# GRBL3-10086-V10.net
KiCad netlist of a schematic drawn in Altium Designer
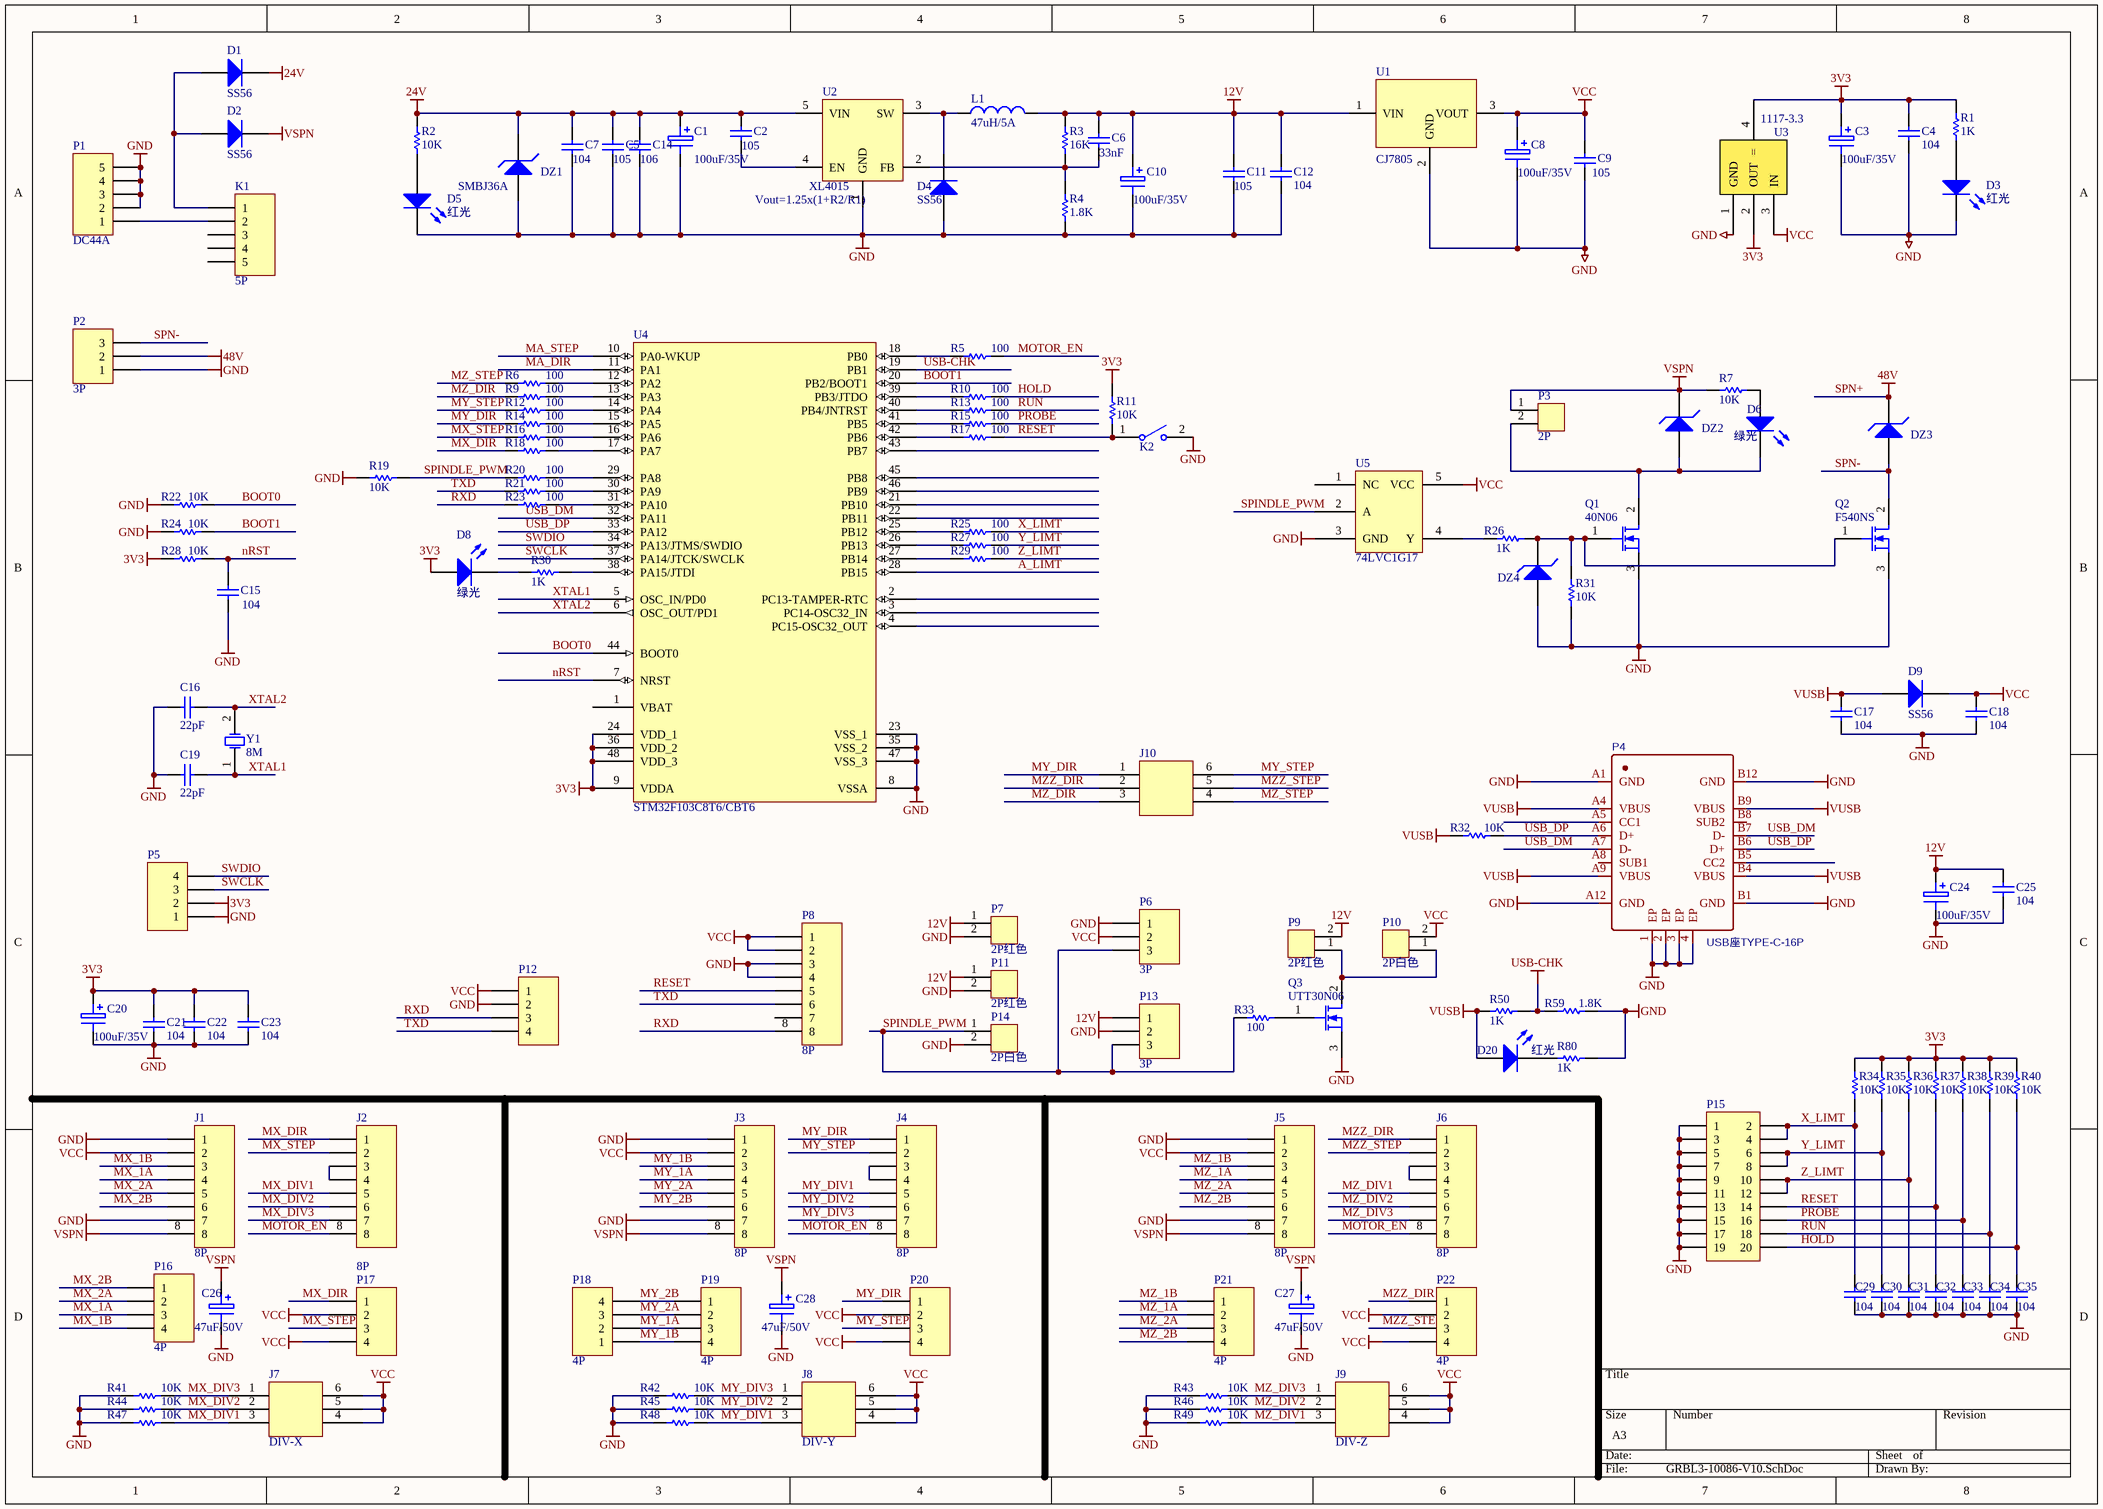
[diagram p0: GRBL3-10086-V10.SchDoc]

(export (version "E")
  (design (tool "Eeschema 10.0.6"))
  (components
    (comp (ref "C1") (value "100uF/35V") (footprint "电解电容贴片6x6") (libsource (lib "*") (part "ELECTRO1")))
    (comp (ref "C2") (value "105") (footprint "0603C") (libsource (lib "SCH封装库") (part "CAP")))
    (comp (ref "C3") (value "100uF/35V") (footprint "电解电容贴片6x6") (libsource (lib "*") (part "ELECTRO1")))
    (comp (ref "C4")
      (value "104")
      (footprint "0603C")
      (description "Capacitor (Semiconductor SIM Model)")
      (fields (field (name "PUBLISHER") "Altium Limited"))
      (libsource (lib "Miscellaneous Devices") (part "Cap Semi"))
    )
    (comp (ref "C5") (value "105") (footprint "0603C") (libsource (lib "SCH封装库") (part "CAP")))
    (comp (ref "C6") (value "33nF") (footprint "0603C") (libsource (lib "SCH封装库") (part "CAP")))
    (comp (ref "C7") (value "104") (footprint "0603C") (libsource (lib "SCH封装库") (part "CAP")))
    (comp (ref "C8") (value "100uF/35V") (footprint "电解电容贴片6x6") (libsource (lib "*") (part "ELECTRO1")))
    (comp (ref "C9")
      (value "105")
      (footprint "0603C")
      (description "Capacitor (Semiconductor SIM Model)")
      (fields (field (name "PUBLISHER") "Altium Limited"))
      (libsource (lib "Miscellaneous Devices") (part "Cap Semi"))
    )
    (comp (ref "C10") (value "100uF/35V") (footprint "电解电容贴片6x6") (libsource (lib "*") (part "ELECTRO1")))
    (comp (ref "C11") (value "105") (footprint "0603C") (libsource (lib "SCH封装库") (part "CAP")))
    (comp (ref "C12")
      (value "104")
      (footprint "0603C")
      (description "Capacitor (Semiconductor SIM Model)")
      (fields (field (name "PUBLISHER") "Altium Limited"))
      (libsource (lib "Miscellaneous Devices") (part "Cap Semi"))
    )
    (comp (ref "C14") (value "106") (footprint "1206C") (libsource (lib "SCH封装库") (part "CAP")))
    (comp (ref "C15")
      (value "104")
      (footprint "0603C")
      (description "Capacitor (Semiconductor SIM Model)")
      (fields (field (name "PUBLISHER") "Altium Limited"))
      (libsource (lib "Miscellaneous Devices") (part "Cap Semi"))
    )
    (comp (ref "C16")
      (value "22pF")
      (footprint "0603C")
      (description "Capacitor (Semiconductor SIM Model)")
      (fields (field (name "PUBLISHER") "Altium Limited"))
      (libsource (lib "Miscellaneous Devices") (part "Cap Semi"))
    )
    (comp (ref "C17")
      (value "104")
      (footprint "0603C")
      (description "Capacitor (Semiconductor SIM Model)")
      (fields (field (name "PUBLISHER") "Altium Limited"))
      (libsource (lib "Miscellaneous Devices") (part "Cap Semi"))
    )
    (comp (ref "C18")
      (value "104")
      (footprint "0603C")
      (description "Capacitor (Semiconductor SIM Model)")
      (fields (field (name "PUBLISHER") "Altium Limited"))
      (libsource (lib "Miscellaneous Devices") (part "Cap Semi"))
    )
    (comp (ref "C19")
      (value "22pF")
      (footprint "0603C")
      (description "Capacitor (Semiconductor SIM Model)")
      (fields (field (name "PUBLISHER") "Altium Limited"))
      (libsource (lib "Miscellaneous Devices") (part "Cap Semi"))
    )
    (comp (ref "C20") (value "100uF/35V") (footprint "电解电容贴片6x6") (libsource (lib "*") (part "ELECTRO1")))
    (comp (ref "C21") (value "104") (footprint "0603C") (libsource (lib "SCH封装库") (part "CAP")))
    (comp (ref "C22") (value "104") (footprint "0603C") (libsource (lib "SCH封装库") (part "CAP")))
    (comp (ref "C23") (value "104") (footprint "0603C") (libsource (lib "SCH封装库") (part "CAP")))
    (comp (ref "C24") (value "100uF/35V") (footprint "电解电容贴片6x6") (libsource (lib "*") (part "ELECTRO1")))
    (comp (ref "C25")
      (value "104")
      (footprint "0603C")
      (description "Capacitor (Semiconductor SIM Model)")
      (fields (field (name "PUBLISHER") "Altium Limited"))
      (libsource (lib "Miscellaneous Devices") (part "Cap Semi"))
    )
    (comp (ref "C26") (value "47uF/50V") (footprint "电解电容贴片6x6") (libsource (lib "*") (part "ELECTRO1")))
    (comp (ref "C27") (value "47uF/50V") (footprint "电解电容贴片6x6") (libsource (lib "*") (part "ELECTRO1")))
    (comp (ref "C28") (value "47uF/50V") (footprint "电解电容贴片6x6") (libsource (lib "*") (part "ELECTRO1")))
    (comp (ref "C29")
      (value "104")
      (footprint "0603C")
      (description "Capacitor (Semiconductor SIM Model)")
      (fields (field (name "PUBLISHER") "Altium Limited"))
      (libsource (lib "Miscellaneous Devices") (part "Cap Semi"))
    )
    (comp (ref "C30")
      (value "104")
      (footprint "0603C")
      (description "Capacitor (Semiconductor SIM Model)")
      (fields (field (name "PUBLISHER") "Altium Limited"))
      (libsource (lib "Miscellaneous Devices") (part "Cap Semi"))
    )
    (comp (ref "C31")
      (value "104")
      (footprint "0603C")
      (description "Capacitor (Semiconductor SIM Model)")
      (fields (field (name "PUBLISHER") "Altium Limited"))
      (libsource (lib "Miscellaneous Devices") (part "Cap Semi"))
    )
    (comp (ref "C32")
      (value "104")
      (footprint "0603C")
      (description "Capacitor (Semiconductor SIM Model)")
      (fields (field (name "PUBLISHER") "Altium Limited"))
      (libsource (lib "Miscellaneous Devices") (part "Cap Semi"))
    )
    (comp (ref "C33")
      (value "104")
      (footprint "0603C")
      (description "Capacitor (Semiconductor SIM Model)")
      (fields (field (name "PUBLISHER") "Altium Limited"))
      (libsource (lib "Miscellaneous Devices") (part "Cap Semi"))
    )
    (comp (ref "C34")
      (value "104")
      (footprint "0603C")
      (description "Capacitor (Semiconductor SIM Model)")
      (fields (field (name "PUBLISHER") "Altium Limited"))
      (libsource (lib "Miscellaneous Devices") (part "Cap Semi"))
    )
    (comp (ref "C35")
      (value "104")
      (footprint "0603C")
      (description "Capacitor (Semiconductor SIM Model)")
      (fields (field (name "PUBLISHER") "Altium Limited"))
      (libsource (lib "Miscellaneous Devices") (part "Cap Semi"))
    )
    (comp (ref "D1") (value "SS56") (footprint "SMA") (libsource (lib "SCH封装库") (part "1N4148")))
    (comp (ref "D2") (value "SS56") (footprint "SMA") (libsource (lib "SCH封装库") (part "1N4148")))
    (comp (ref "D3") (value "红光") (footprint "0603LED") (libsource (lib "SCH封装库") (part "LED")))
    (comp (ref "D4") (value "SS56") (footprint "SMA") (libsource (lib "SCH封装库") (part "1N4148")))
    (comp (ref "D5") (value "红光") (footprint "0603LED") (libsource (lib "SCH封装库") (part "LED")))
    (comp (ref "D6") (value "绿光") (footprint "0603LED") (libsource (lib "SCH封装库") (part "LED")))
    (comp (ref "D8") (value "绿光") (footprint "0603LED") (libsource (lib "SCH封装库") (part "LED")))
    (comp (ref "D9") (value "SS56") (footprint "SMA") (libsource (lib "SCH封装库") (part "1N4148")))
    (comp (ref "D20") (value "红光") (footprint "0603LED") (libsource (lib "SCH封装库") (part "LED")))
    (comp (ref "DZ1") (value "SMBJ36A") (footprint "SMB") (libsource (lib "SCH封装库") (part "稳压二极管")))
    (comp (ref "DZ2") (value "快恢复二极管RS5M") (footprint "SMC") (libsource (lib "SCH封装库") (part "稳压二极管")))
    (comp (ref "DZ3") (value "快恢复二极管RS5M") (footprint "SMC") (libsource (lib "SCH封装库") (part "稳压二极管")))
    (comp (ref "DZ4") (value "稳压二极管SMAZ10V") (footprint "SMA") (libsource (lib "SCH封装库") (part "稳压二极管")))
    (comp (ref "J1") (value "8P") (footprint "HDR1X8") (libsource (lib "SCH封装库") (part "8P")))
    (comp (ref "J2") (value "8P") (footprint "HDR1X8") (libsource (lib "SCH封装库") (part "8P")))
    (comp (ref "J3") (value "8P") (footprint "HDR1X8") (libsource (lib "SCH封装库") (part "8P")))
    (comp (ref "J4") (value "8P") (footprint "HDR1X8") (libsource (lib "SCH封装库") (part "8P")))
    (comp (ref "J5") (value "8P") (footprint "HDR1X8") (libsource (lib "SCH封装库") (part "8P")))
    (comp (ref "J6") (value "8P") (footprint "HDR1X8") (libsource (lib "SCH封装库") (part "8P")))
    (comp (ref "J7") (value "DIV-X") (footprint "HDR2X3") (libsource (lib "SCH封装库") (part "DIP6")))
    (comp (ref "J8") (value "DIV-Y") (footprint "HDR2X3") (libsource (lib "SCH封装库") (part "DIP6")))
    (comp (ref "J9") (value "DIV-Z") (footprint "HDR2X3") (libsource (lib "SCH封装库") (part "DIP6")))
    (comp (ref "J10") (value "DIV-Y") (footprint "HDR2X3") (libsource (lib "SCH封装库") (part "DIP6")))
    (comp (ref "K1") (value "5P") (footprint "拨动开关SS12D11") (libsource (lib "SCH封装库") (part "5P")))
    (comp (ref "K2") (value "开关") (footprint "按键6x6贴片5脚") (libsource (lib "SCH封装库") (part "开关")))
    (comp (ref "L1")
      (value "47uH/5A")
      (footprint "电感贴片12x12")
      (description "Inductor")
      (fields (field (name "PUBLISHER") "Altium Limited"))
      (libsource (lib "SCH封装库") (part "Inductor"))
    )
    (comp (ref "P1")
      (value "DC44A")
      (footprint "DC0044A")
      (description "Header, 5-Pin")
      (fields (field (name "PUBLISHER") "Altium Limited"))
      (libsource (lib "Miscellaneous Connectors") (part "Header 5"))
    )
    (comp (ref "P2") (value "3P") (footprint "直插座3P-KF300") (libsource (lib "") (part "3P_1")))
    (comp (ref "P3") (value "2P") (footprint "VH3.96-2P直插座") (libsource (lib "SCH封装库") (part "2P")))
    (comp (ref "P4")
      (value "USB座TYPE-C-16P")
      (footprint "USB-TYPE-C-16P")
      (fields
        (field (name "BOM_SUPPLIER PART") "C709358")
        (field (name "BOM_MANUFACTURER PART") "KH-TYPE-C-16P-T")
        (field (name "CONTRIBUTOR") "LCSC")
      )
      (libsource (lib "SCH封装库") (part "USB座TYPE-C-16P"))
    )
    (comp (ref "P5") (value "~") (footprint "SIP4") (libsource (lib "") (part "4P_1")))
    (comp (ref "P6") (value "3P") (footprint "SIP3") (libsource (lib "SCH封装库") (part "3P")))
    (comp (ref "P7") (value "2P红色") (footprint "HDR1X2_CON") (libsource (lib "SCH封装库") (part "2P")))
    (comp (ref "P8") (value "8P") (footprint "IDC8") (libsource (lib "SCH封装库") (part "8P")))
    (comp (ref "P9") (value "2P红色") (footprint "HDR1X2_CON") (libsource (lib "") (part "2P_1")))
    (comp (ref "P10") (value "2P白色") (footprint "HDR1X2_CON") (libsource (lib "") (part "2P_1")))
    (comp (ref "P11") (value "2P红色") (footprint "HDR1X2_CON") (libsource (lib "SCH封装库") (part "2P")))
    (comp (ref "P12") (value "~") (footprint "SIP4") (libsource (lib "SCH封装库") (part "4P")))
    (comp (ref "P13") (value "3P") (footprint "HDR1X3_CON") (libsource (lib "SCH封装库") (part "3P")))
    (comp (ref "P14") (value "2P白色") (footprint "HDR1X2_CON") (libsource (lib "SCH封装库") (part "2P")))
    (comp (ref "P15")
      (value "Header 10X2H")
      (footprint "HDR2X10")
      (description "Header, 10-Pin, Dual row, Right Angle")
      (fields (field (name "PUBLISHER") "Altium Limited"))
      (libsource (lib "Miscellaneous Connectors") (part "Header 10X2H"))
    )
    (comp (ref "P16") (value "4P") (footprint "HDR1X4_CON") (libsource (lib "SCH封装库") (part "4P")))
    (comp (ref "P17") (value "~") (footprint "SIP4") (libsource (lib "SCH封装库") (part "4P")))
    (comp (ref "P18") (value "4P") (footprint "HDR1X4_CON") (libsource (lib "") (part "4P_1")))
    (comp (ref "P19") (value "4P") (footprint "HDR1X4_CON") (libsource (lib "SCH封装库") (part "4P")))
    (comp (ref "P20") (value "~") (footprint "SIP4") (libsource (lib "SCH封装库") (part "4P")))
    (comp (ref "P21") (value "4P") (footprint "HDR1X4_CON") (libsource (lib "SCH封装库") (part "4P")))
    (comp (ref "P22") (value "4P") (footprint "SIP4") (libsource (lib "SCH封装库") (part "4P")))
    (comp (ref "Q1")
      (value "40N06")
      (footprint "TO-252")
      (description "N-Channel MOSFET")
      (fields (field (name "PUBLISHER") "Altium Limited"))
      (libsource (lib "SCH封装库") (part "MOSFET-N"))
    )
    (comp (ref "Q2")
      (value "F540NS")
      (footprint "TO-263-2")
      (description "N-Channel MOSFET")
      (fields (field (name "PUBLISHER") "Altium Limited"))
      (libsource (lib "SCH封装库") (part "MOSFET-N"))
    )
    (comp (ref "Q3")
      (value "UTT30N06")
      (footprint "TO-252")
      (description "N-Channel MOSFET")
      (fields (field (name "PUBLISHER") "Altium Limited"))
      (libsource (lib "SCH封装库") (part "MOSFET-N"))
    )
    (comp (ref "R1")
      (value "1K")
      (footprint "0603R")
      (description "Resistor")
      (fields (field (name "PUBLISHER") "Altium Limited"))
      (libsource (lib "SCH封装库") (part "RES"))
    )
    (comp (ref "R2")
      (value "10K")
      (footprint "0603R")
      (description "Resistor")
      (fields (field (name "PUBLISHER") "Altium Limited"))
      (libsource (lib "SCH封装库") (part "RES"))
    )
    (comp (ref "R3")
      (value "16K")
      (footprint "0603R")
      (description "Resistor")
      (fields (field (name "PUBLISHER") "Altium Limited"))
      (libsource (lib "SCH封装库") (part "RES"))
    )
    (comp (ref "R4")
      (value "1.8K")
      (footprint "0603R")
      (description "Resistor")
      (fields (field (name "PUBLISHER") "Altium Limited"))
      (libsource (lib "SCH封装库") (part "RES"))
    )
    (comp (ref "R5")
      (value "100")
      (footprint "0603R")
      (description "Resistor")
      (fields (field (name "PUBLISHER") "Altium Limited"))
      (libsource (lib "SCH封装库") (part "RES"))
    )
    (comp (ref "R6")
      (value "100")
      (footprint "0603R")
      (description "Resistor")
      (fields (field (name "PUBLISHER") "Altium Limited"))
      (libsource (lib "SCH封装库") (part "RES"))
    )
    (comp (ref "R7")
      (value "10K")
      (footprint "0603R")
      (description "Resistor")
      (fields (field (name "PUBLISHER") "Altium Limited"))
      (libsource (lib "SCH封装库") (part "RES"))
    )
    (comp (ref "R9")
      (value "100")
      (footprint "0603R")
      (description "Resistor")
      (fields (field (name "PUBLISHER") "Altium Limited"))
      (libsource (lib "SCH封装库") (part "RES"))
    )
    (comp (ref "R10")
      (value "100")
      (footprint "0603R")
      (description "Resistor")
      (fields (field (name "PUBLISHER") "Altium Limited"))
      (libsource (lib "SCH封装库") (part "RES"))
    )
    (comp (ref "R11")
      (value "10K")
      (footprint "0603R")
      (description "Resistor")
      (fields (field (name "PUBLISHER") "Altium Limited"))
      (libsource (lib "SCH封装库") (part "RES"))
    )
    (comp (ref "R12")
      (value "100")
      (footprint "0603R")
      (description "Resistor")
      (fields (field (name "PUBLISHER") "Altium Limited"))
      (libsource (lib "SCH封装库") (part "RES"))
    )
    (comp (ref "R13")
      (value "100")
      (footprint "0603R")
      (description "Resistor")
      (fields (field (name "PUBLISHER") "Altium Limited"))
      (libsource (lib "SCH封装库") (part "RES"))
    )
    (comp (ref "R14")
      (value "100")
      (footprint "0603R")
      (description "Resistor")
      (fields (field (name "PUBLISHER") "Altium Limited"))
      (libsource (lib "SCH封装库") (part "RES"))
    )
    (comp (ref "R15")
      (value "100")
      (footprint "0603R")
      (description "Resistor")
      (fields (field (name "PUBLISHER") "Altium Limited"))
      (libsource (lib "SCH封装库") (part "RES"))
    )
    (comp (ref "R16")
      (value "100")
      (footprint "0603R")
      (description "Resistor")
      (fields (field (name "PUBLISHER") "Altium Limited"))
      (libsource (lib "SCH封装库") (part "RES"))
    )
    (comp (ref "R17")
      (value "100")
      (footprint "0603R")
      (description "Resistor")
      (fields (field (name "PUBLISHER") "Altium Limited"))
      (libsource (lib "SCH封装库") (part "RES"))
    )
    (comp (ref "R18")
      (value "100")
      (footprint "0603R")
      (description "Resistor")
      (fields (field (name "PUBLISHER") "Altium Limited"))
      (libsource (lib "SCH封装库") (part "RES"))
    )
    (comp (ref "R19")
      (value "10K")
      (footprint "0603R")
      (description "Resistor")
      (fields (field (name "PUBLISHER") "Altium Limited"))
      (libsource (lib "SCH封装库") (part "RES"))
    )
    (comp (ref "R20")
      (value "100")
      (footprint "0603R")
      (description "Resistor")
      (fields (field (name "PUBLISHER") "Altium Limited"))
      (libsource (lib "SCH封装库") (part "RES"))
    )
    (comp (ref "R21")
      (value "100")
      (footprint "0603R")
      (description "Resistor")
      (fields (field (name "PUBLISHER") "Altium Limited"))
      (libsource (lib "SCH封装库") (part "RES"))
    )
    (comp (ref "R22")
      (value "10K")
      (footprint "0603R")
      (description "Resistor")
      (fields (field (name "Comment") "10k") (field (name "PUBLISHER") "Altium Limited"))
      (libsource (lib "SCH封装库") (part "RES"))
    )
    (comp (ref "R23")
      (value "100")
      (footprint "0603R")
      (description "Resistor")
      (fields (field (name "PUBLISHER") "Altium Limited"))
      (libsource (lib "SCH封装库") (part "RES"))
    )
    (comp (ref "R24")
      (value "10K")
      (footprint "0603R")
      (description "Resistor")
      (fields (field (name "Comment") "10k") (field (name "PUBLISHER") "Altium Limited"))
      (libsource (lib "SCH封装库") (part "RES"))
    )
    (comp (ref "R25")
      (value "100")
      (footprint "0603R")
      (description "Resistor")
      (fields (field (name "PUBLISHER") "Altium Limited"))
      (libsource (lib "SCH封装库") (part "RES"))
    )
    (comp (ref "R26")
      (value "1K")
      (footprint "0603R")
      (description "Resistor")
      (fields (field (name "PUBLISHER") "Altium Limited"))
      (libsource (lib "SCH封装库") (part "RES"))
    )
    (comp (ref "R27")
      (value "100")
      (footprint "0603R")
      (description "Resistor")
      (fields (field (name "PUBLISHER") "Altium Limited"))
      (libsource (lib "SCH封装库") (part "RES"))
    )
    (comp (ref "R28")
      (value "10K")
      (footprint "0603R")
      (description "Resistor")
      (fields (field (name "Comment") "10k") (field (name "PUBLISHER") "Altium Limited"))
      (libsource (lib "SCH封装库") (part "RES"))
    )
    (comp (ref "R29")
      (value "100")
      (footprint "0603R")
      (description "Resistor")
      (fields (field (name "PUBLISHER") "Altium Limited"))
      (libsource (lib "SCH封装库") (part "RES"))
    )
    (comp (ref "R30")
      (value "1K")
      (footprint "0603R")
      (description "Resistor")
      (fields (field (name "PUBLISHER") "Altium Limited"))
      (libsource (lib "SCH封装库") (part "RES"))
    )
    (comp (ref "R31")
      (value "10K")
      (footprint "0603R")
      (description "Resistor")
      (fields (field (name "PUBLISHER") "Altium Limited"))
      (libsource (lib "SCH封装库") (part "RES"))
    )
    (comp (ref "R32")
      (value "10K")
      (footprint "0603R")
      (description "Resistor")
      (fields (field (name "PUBLISHER") "Altium Limited"))
      (libsource (lib "SCH封装库") (part "RES"))
    )
    (comp (ref "R33")
      (value "100")
      (footprint "0603R")
      (description "Resistor")
      (fields (field (name "PUBLISHER") "Altium Limited"))
      (libsource (lib "SCH封装库") (part "RES"))
    )
    (comp (ref "R34")
      (value "10K")
      (footprint "0603R")
      (description "Resistor")
      (fields (field (name "PUBLISHER") "Altium Limited"))
      (libsource (lib "SCH封装库") (part "RES"))
    )
    (comp (ref "R35")
      (value "10K")
      (footprint "0603R")
      (description "Resistor")
      (fields (field (name "PUBLISHER") "Altium Limited"))
      (libsource (lib "SCH封装库") (part "RES"))
    )
    (comp (ref "R36")
      (value "10K")
      (footprint "0603R")
      (description "Resistor")
      (fields (field (name "PUBLISHER") "Altium Limited"))
      (libsource (lib "SCH封装库") (part "RES"))
    )
    (comp (ref "R37")
      (value "10K")
      (footprint "0603R")
      (description "Resistor")
      (fields (field (name "PUBLISHER") "Altium Limited"))
      (libsource (lib "SCH封装库") (part "RES"))
    )
    (comp (ref "R38")
      (value "10K")
      (footprint "0603R")
      (description "Resistor")
      (fields (field (name "PUBLISHER") "Altium Limited"))
      (libsource (lib "SCH封装库") (part "RES"))
    )
    (comp (ref "R39")
      (value "10K")
      (footprint "0603R")
      (description "Resistor")
      (fields (field (name "PUBLISHER") "Altium Limited"))
      (libsource (lib "SCH封装库") (part "RES"))
    )
    (comp (ref "R40")
      (value "10K")
      (footprint "0603R")
      (description "Resistor")
      (fields (field (name "PUBLISHER") "Altium Limited"))
      (libsource (lib "SCH封装库") (part "RES"))
    )
    (comp (ref "R41")
      (value "10K")
      (footprint "0603R")
      (description "Resistor")
      (fields (field (name "PUBLISHER") "Altium Limited"))
      (libsource (lib "SCH封装库") (part "RES"))
    )
    (comp (ref "R42")
      (value "10K")
      (footprint "0603R")
      (description "Resistor")
      (fields (field (name "PUBLISHER") "Altium Limited"))
      (libsource (lib "SCH封装库") (part "RES"))
    )
    (comp (ref "R43")
      (value "10K")
      (footprint "0603R")
      (description "Resistor")
      (fields (field (name "PUBLISHER") "Altium Limited"))
      (libsource (lib "SCH封装库") (part "RES"))
    )
    (comp (ref "R44")
      (value "10K")
      (footprint "0603R")
      (description "Resistor")
      (fields (field (name "PUBLISHER") "Altium Limited"))
      (libsource (lib "SCH封装库") (part "RES"))
    )
    (comp (ref "R45")
      (value "10K")
      (footprint "0603R")
      (description "Resistor")
      (fields (field (name "PUBLISHER") "Altium Limited"))
      (libsource (lib "SCH封装库") (part "RES"))
    )
    (comp (ref "R46")
      (value "10K")
      (footprint "0603R")
      (description "Resistor")
      (fields (field (name "PUBLISHER") "Altium Limited"))
      (libsource (lib "SCH封装库") (part "RES"))
    )
    (comp (ref "R47")
      (value "10K")
      (footprint "0603R")
      (description "Resistor")
      (fields (field (name "PUBLISHER") "Altium Limited"))
      (libsource (lib "SCH封装库") (part "RES"))
    )
    (comp (ref "R48")
      (value "10K")
      (footprint "0603R")
      (description "Resistor")
      (fields (field (name "PUBLISHER") "Altium Limited"))
      (libsource (lib "SCH封装库") (part "RES"))
    )
    (comp (ref "R49")
      (value "10K")
      (footprint "0603R")
      (description "Resistor")
      (fields (field (name "PUBLISHER") "Altium Limited"))
      (libsource (lib "SCH封装库") (part "RES"))
    )
    (comp (ref "R50")
      (value "1K")
      (footprint "0603R")
      (description "Resistor")
      (fields (field (name "PUBLISHER") "Altium Limited"))
      (libsource (lib "SCH封装库") (part "RES"))
    )
    (comp (ref "R59")
      (value "1.8K")
      (footprint "0603R")
      (description "Resistor")
      (fields (field (name "PUBLISHER") "Altium Limited"))
      (libsource (lib "SCH封装库") (part "RES"))
    )
    (comp (ref "R80")
      (value "1K")
      (footprint "0603R")
      (description "Resistor")
      (fields (field (name "PUBLISHER") "Altium Limited"))
      (libsource (lib "SCH封装库") (part "RES"))
    )
    (comp (ref "U1") (value "CJ7805") (footprint "TO-263-2") (libsource (lib "SCH封装库") (part "7805")))
    (comp (ref "U2") (value "XL4015") (footprint "TO-263") (libsource (lib "SCH封装库") (part "XL4005")))
    (comp (ref "U3") (value "1117-3.3") (footprint "SOT-223") (libsource (lib "Party600") (part "LM1117")))
    (comp (ref "U4")
      (value "STM32F103C8T6/CBT6")
      (footprint "LQFP48")
      (description "STM32 ARM-based 32-bit MCU with 32 Kbytes Flash, 48-pin LQFP, Industrial Temperature")
      (fields (field (name "PUBLISHER") "*"))
      (libsource (lib "ST Microcontroller 32-Bit STM32 SCH") (part "STM32F103C6T6"))
    )
    (comp (ref "U5") (value "74LVC1G17") (footprint "SOT-23-5") (libsource (lib "SCH封装库") (part "74LVC1G17")))
    (comp (ref "Y1")
      (value "8M")
      (footprint "晶振贴片")
      (description "Crystal Oscillator")
      (fields (field (name "PUBLISHER") "Altium Limited"))
      (libsource (lib "Miscellaneous Devices") (part "XTAL"))
    )
  )
  (nets
    (net (code "1") (name "/A_LIMT") (class "Default")
      (node (ref "U4") (pin "28") (pinfunction "PB15_28") (pintype "bidirectional"))
    )
    (net (code "2") (name "/BOOT0") (class "Default")
      (node (ref "R22") (pin "2") (pinfunction "2_2") (pintype "passive"))
      (node (ref "U4") (pin "44") (pinfunction "BOOT0_44") (pintype "input"))
    )
    (net (code "3") (name "/BOOT1") (class "Default")
      (node (ref "R24") (pin "2") (pinfunction "2_2") (pintype "passive"))
      (node (ref "U4") (pin "20") (pinfunction "PB2/BOOT1_20") (pintype "bidirectional"))
    )
    (net (code "4") (name "/HOLD") (class "Default")
      (node (ref "C35") (pin "2") (pinfunction "2_2") (pintype "passive"))
      (node (ref "P15") (pin "20") (pinfunction "20_20") (pintype "passive"))
      (node (ref "R10") (pin "2") (pinfunction "2_2") (pintype "passive"))
      (node (ref "R40") (pin "1") (pinfunction "1_1") (pintype "passive"))
    )
    (net (code "5") (name "/MA_DIR") (class "Default")
      (node (ref "U4") (pin "11") (pinfunction "PA1_11") (pintype "bidirectional"))
    )
    (net (code "6") (name "/MA_STEP") (class "Default")
      (node (ref "U4") (pin "10") (pinfunction "PA0-WKUP_10") (pintype "bidirectional"))
    )
    (net (code "7") (name "/MOTOR_EN") (class "Default")
      (node (ref "J2") (pin "8") (pinfunction "8_8") (pintype "passive"))
      (node (ref "J4") (pin "8") (pinfunction "8_8") (pintype "passive"))
      (node (ref "J6") (pin "8") (pinfunction "8_8") (pintype "passive"))
      (node (ref "R5") (pin "2") (pinfunction "2_2") (pintype "passive"))
    )
    (net (code "8") (name "/MX_1A") (class "Default")
      (node (ref "J1") (pin "4") (pinfunction "4_4") (pintype "passive"))
      (node (ref "P16") (pin "3") (pinfunction "3_3") (pintype "passive"))
    )
    (net (code "9") (name "/MX_1B") (class "Default")
      (node (ref "J1") (pin "3") (pinfunction "3_3") (pintype "passive"))
      (node (ref "P16") (pin "4") (pinfunction "4_4") (pintype "passive"))
    )
    (net (code "10") (name "/MX_2A") (class "Default")
      (node (ref "J1") (pin "5") (pinfunction "5_5") (pintype "passive"))
      (node (ref "P16") (pin "2") (pinfunction "2_2") (pintype "passive"))
    )
    (net (code "11") (name "/MX_2B") (class "Default")
      (node (ref "J1") (pin "6") (pinfunction "6_6") (pintype "passive"))
      (node (ref "P16") (pin "1") (pinfunction "1_1") (pintype "passive"))
    )
    (net (code "12") (name "/MX_DIR") (class "Default")
      (node (ref "J2") (pin "1") (pinfunction "1_1") (pintype "passive"))
      (node (ref "P17") (pin "1") (pinfunction "1_1") (pintype "passive"))
      (node (ref "R18") (pin "1") (pinfunction "1_1") (pintype "passive"))
    )
    (net (code "13") (name "/MX_DIV1") (class "Default")
      (node (ref "J2") (pin "5") (pinfunction "5_5") (pintype "passive"))
      (node (ref "J7") (pin "3") (pinfunction "3_3") (pintype "passive"))
      (node (ref "R47") (pin "1") (pinfunction "1_1") (pintype "passive"))
    )
    (net (code "14") (name "/MX_DIV2") (class "Default")
      (node (ref "J2") (pin "6") (pinfunction "6_6") (pintype "passive"))
      (node (ref "J7") (pin "2") (pinfunction "2_2") (pintype "passive"))
      (node (ref "R44") (pin "1") (pinfunction "1_1") (pintype "passive"))
    )
    (net (code "15") (name "/MX_DIV3") (class "Default")
      (node (ref "J2") (pin "7") (pinfunction "7_7") (pintype "passive"))
      (node (ref "J7") (pin "1") (pinfunction "1_1") (pintype "passive"))
      (node (ref "R41") (pin "1") (pinfunction "1_1") (pintype "passive"))
    )
    (net (code "16") (name "/MX_STEP") (class "Default")
      (node (ref "J2") (pin "2") (pinfunction "2_2") (pintype "passive"))
      (node (ref "P17") (pin "3") (pinfunction "3_3") (pintype "passive"))
      (node (ref "R16") (pin "1") (pinfunction "1_1") (pintype "passive"))
    )
    (net (code "17") (name "/MY_1A") (class "Default")
      (node (ref "J3") (pin "4") (pinfunction "4_4") (pintype "passive"))
      (node (ref "P18") (pin "2") (pinfunction "2_2") (pintype "passive"))
      (node (ref "P19") (pin "3") (pinfunction "3_3") (pintype "passive"))
    )
    (net (code "18") (name "/MY_1B") (class "Default")
      (node (ref "J3") (pin "3") (pinfunction "3_3") (pintype "passive"))
      (node (ref "P18") (pin "1") (pinfunction "1_1") (pintype "passive"))
      (node (ref "P19") (pin "4") (pinfunction "4_4") (pintype "passive"))
    )
    (net (code "19") (name "/MY_2A") (class "Default")
      (node (ref "J3") (pin "5") (pinfunction "5_5") (pintype "passive"))
      (node (ref "P18") (pin "3") (pinfunction "3_3") (pintype "passive"))
      (node (ref "P19") (pin "2") (pinfunction "2_2") (pintype "passive"))
    )
    (net (code "20") (name "/MY_2B") (class "Default")
      (node (ref "J3") (pin "6") (pinfunction "6_6") (pintype "passive"))
      (node (ref "P18") (pin "4") (pinfunction "4_4") (pintype "passive"))
      (node (ref "P19") (pin "1") (pinfunction "1_1") (pintype "passive"))
    )
    (net (code "21") (name "/MY_DIR") (class "Default")
      (node (ref "J10") (pin "1") (pinfunction "1_1") (pintype "passive"))
      (node (ref "J4") (pin "1") (pinfunction "1_1") (pintype "passive"))
      (node (ref "P20") (pin "1") (pinfunction "1_1") (pintype "passive"))
      (node (ref "R14") (pin "1") (pinfunction "1_1") (pintype "passive"))
    )
    (net (code "22") (name "/MY_DIV1") (class "Default")
      (node (ref "J4") (pin "5") (pinfunction "5_5") (pintype "passive"))
      (node (ref "J8") (pin "3") (pinfunction "3_3") (pintype "passive"))
      (node (ref "R48") (pin "1") (pinfunction "1_1") (pintype "passive"))
    )
    (net (code "23") (name "/MY_DIV2") (class "Default")
      (node (ref "J4") (pin "6") (pinfunction "6_6") (pintype "passive"))
      (node (ref "J8") (pin "2") (pinfunction "2_2") (pintype "passive"))
      (node (ref "R45") (pin "1") (pinfunction "1_1") (pintype "passive"))
    )
    (net (code "24") (name "/MY_DIV3") (class "Default")
      (node (ref "J4") (pin "7") (pinfunction "7_7") (pintype "passive"))
      (node (ref "J8") (pin "1") (pinfunction "1_1") (pintype "passive"))
      (node (ref "R42") (pin "1") (pinfunction "1_1") (pintype "passive"))
    )
    (net (code "25") (name "/MY_STEP") (class "Default")
      (node (ref "J10") (pin "6") (pinfunction "6_6") (pintype "passive"))
      (node (ref "J4") (pin "2") (pinfunction "2_2") (pintype "passive"))
      (node (ref "P20") (pin "3") (pinfunction "3_3") (pintype "passive"))
      (node (ref "R12") (pin "1") (pinfunction "1_1") (pintype "passive"))
    )
    (net (code "26") (name "/MZZ_DIR") (class "Default")
      (node (ref "J10") (pin "2") (pinfunction "2_2") (pintype "passive"))
      (node (ref "J6") (pin "1") (pinfunction "1_1") (pintype "passive"))
      (node (ref "P22") (pin "1") (pinfunction "1_1") (pintype "passive"))
    )
    (net (code "27") (name "/MZZ_STEP") (class "Default")
      (node (ref "J10") (pin "5") (pinfunction "5_5") (pintype "passive"))
      (node (ref "J6") (pin "2") (pinfunction "2_2") (pintype "passive"))
      (node (ref "P22") (pin "3") (pinfunction "3_3") (pintype "passive"))
    )
    (net (code "28") (name "/MZ_1A") (class "Default")
      (node (ref "J5") (pin "4") (pinfunction "4_4") (pintype "passive"))
      (node (ref "P21") (pin "2") (pinfunction "2_2") (pintype "passive"))
    )
    (net (code "29") (name "/MZ_1B") (class "Default")
      (node (ref "J5") (pin "3") (pinfunction "3_3") (pintype "passive"))
      (node (ref "P21") (pin "1") (pinfunction "1_1") (pintype "passive"))
    )
    (net (code "30") (name "/MZ_2A") (class "Default")
      (node (ref "J5") (pin "5") (pinfunction "5_5") (pintype "passive"))
      (node (ref "P21") (pin "3") (pinfunction "3_3") (pintype "passive"))
    )
    (net (code "31") (name "/MZ_2B") (class "Default")
      (node (ref "J5") (pin "6") (pinfunction "6_6") (pintype "passive"))
      (node (ref "P21") (pin "4") (pinfunction "4_4") (pintype "passive"))
    )
    (net (code "32") (name "/MZ_DIR") (class "Default")
      (node (ref "J10") (pin "3") (pinfunction "3_3") (pintype "passive"))
      (node (ref "R9") (pin "1") (pinfunction "1_1") (pintype "passive"))
    )
    (net (code "33") (name "/MZ_DIV1") (class "Default")
      (node (ref "J6") (pin "5") (pinfunction "5_5") (pintype "passive"))
      (node (ref "J9") (pin "3") (pinfunction "3_3") (pintype "passive"))
      (node (ref "R49") (pin "1") (pinfunction "1_1") (pintype "passive"))
    )
    (net (code "34") (name "/MZ_DIV2") (class "Default")
      (node (ref "J6") (pin "6") (pinfunction "6_6") (pintype "passive"))
      (node (ref "J9") (pin "2") (pinfunction "2_2") (pintype "passive"))
      (node (ref "R46") (pin "1") (pinfunction "1_1") (pintype "passive"))
    )
    (net (code "35") (name "/MZ_DIV3") (class "Default")
      (node (ref "J6") (pin "7") (pinfunction "7_7") (pintype "passive"))
      (node (ref "J9") (pin "1") (pinfunction "1_1") (pintype "passive"))
      (node (ref "R43") (pin "1") (pinfunction "1_1") (pintype "passive"))
    )
    (net (code "36") (name "/MZ_STEP") (class "Default")
      (node (ref "J10") (pin "4") (pinfunction "4_4") (pintype "passive"))
      (node (ref "R6") (pin "1") (pinfunction "1_1") (pintype "passive"))
    )
    (net (code "37") (name "/PROBE") (class "Default")
      (node (ref "C33") (pin "2") (pinfunction "2_2") (pintype "passive"))
      (node (ref "P15") (pin "16") (pinfunction "16_16") (pintype "passive"))
      (node (ref "R15") (pin "2") (pinfunction "2_2") (pintype "passive"))
      (node (ref "R38") (pin "1") (pinfunction "1_1") (pintype "passive"))
    )
    (net (code "38") (name "/RESET") (class "Default")
      (node (ref "C32") (pin "2") (pinfunction "2_2") (pintype "passive"))
      (node (ref "K2") (pin "1") (pinfunction "COMMON_1") (pintype "passive"))
      (node (ref "P15") (pin "14") (pinfunction "14_14") (pintype "passive"))
      (node (ref "P8") (pin "5") (pinfunction "5_5") (pintype "passive"))
      (node (ref "R11") (pin "1") (pinfunction "1_1") (pintype "passive"))
      (node (ref "R17") (pin "2") (pinfunction "2_2") (pintype "passive"))
      (node (ref "R37") (pin "1") (pinfunction "1_1") (pintype "passive"))
    )
    (net (code "39") (name "/RUN") (class "Default")
      (node (ref "C34") (pin "2") (pinfunction "2_2") (pintype "passive"))
      (node (ref "P15") (pin "18") (pinfunction "18_18") (pintype "passive"))
      (node (ref "R13") (pin "2") (pinfunction "2_2") (pintype "passive"))
      (node (ref "R39") (pin "1") (pinfunction "1_1") (pintype "passive"))
    )
    (net (code "40") (name "/RXD") (class "Default")
      (node (ref "P12") (pin "3") (pinfunction "3_3") (pintype "passive"))
      (node (ref "P8") (pin "8") (pinfunction "8_8") (pintype "passive"))
      (node (ref "R23") (pin "1") (pinfunction "1_1") (pintype "passive"))
    )
    (net (code "41") (name "/SPINDLE_PWM") (class "Default")
      (node (ref "P13") (pin "3") (pinfunction "3_3") (pintype "passive"))
      (node (ref "P14") (pin "1") (pintype "passive"))
      (node (ref "P6") (pin "3") (pinfunction "3_3") (pintype "passive"))
      (node (ref "R19") (pin "1") (pinfunction "1_1") (pintype "passive"))
      (node (ref "R20") (pin "1") (pinfunction "1_1") (pintype "passive"))
      (node (ref "R33") (pin "1") (pinfunction "1_1") (pintype "passive"))
      (node (ref "U5") (pin "2") (pinfunction "A_2") (pintype "passive"))
    )
    (net (code "42") (name "/SPN-") (class "Default")
      (node (ref "DZ3") (pin "1") (pinfunction "1_1") (pintype "passive"))
      (node (ref "P2") (pin "3") (pinfunction "3_3") (pintype "passive"))
      (node (ref "Q2") (pin "2") (pinfunction "D_2") (pintype "passive"))
    )
    (net (code "43") (name "/SWCLK") (class "Default")
      (node (ref "P5") (pin "3") (pinfunction "3_3") (pintype "passive"))
      (node (ref "U4") (pin "37") (pinfunction "PA14/JTCK/SWCLK_37") (pintype "bidirectional"))
    )
    (net (code "44") (name "/SWDIO") (class "Default")
      (node (ref "P5") (pin "4") (pinfunction "4_4") (pintype "passive"))
      (node (ref "U4") (pin "34") (pinfunction "PA13/JTMS/SWDIO_34") (pintype "bidirectional"))
    )
    (net (code "45") (name "/TXD") (class "Default")
      (node (ref "P12") (pin "4") (pinfunction "4_4") (pintype "passive"))
      (node (ref "P8") (pin "6") (pinfunction "6_6") (pintype "passive"))
      (node (ref "R21") (pin "1") (pinfunction "1_1") (pintype "passive"))
    )
    (net (code "46") (name "/USB_DM") (class "Default")
      (node (ref "P4") (pin "A7") (pinfunction "D-_A7") (pintype "passive"))
      (node (ref "P4") (pin "B7") (pinfunction "D-_B7") (pintype "passive"))
      (node (ref "U4") (pin "32") (pinfunction "PA11_32") (pintype "bidirectional"))
    )
    (net (code "47") (name "/USB_DP") (class "Default")
      (node (ref "P4") (pin "A6") (pinfunction "D+_A6") (pintype "passive"))
      (node (ref "P4") (pin "B6") (pinfunction "D+_B6") (pintype "passive"))
      (node (ref "R32") (pin "2") (pinfunction "2_2") (pintype "passive"))
      (node (ref "U4") (pin "33") (pinfunction "PA12_33") (pintype "bidirectional"))
    )
    (net (code "48") (name "/XTAL1") (class "Default")
      (node (ref "C19") (pin "1") (pinfunction "1_1") (pintype "passive"))
      (node (ref "U4") (pin "5") (pinfunction "OSC_IN/PD0_5") (pintype "input"))
      (node (ref "Y1") (pin "1") (pinfunction "OSC1_1") (pintype "passive"))
    )
    (net (code "49") (name "/XTAL2") (class "Default")
      (node (ref "C16") (pin "1") (pinfunction "1_1") (pintype "passive"))
      (node (ref "U4") (pin "6") (pinfunction "OSC_OUT/PD1_6") (pintype "output"))
      (node (ref "Y1") (pin "2") (pinfunction "OSC2_2") (pintype "passive"))
    )
    (net (code "50") (name "/X_LIMT") (class "Default")
      (node (ref "C29") (pin "2") (pinfunction "2_2") (pintype "passive"))
      (node (ref "P15") (pin "2") (pinfunction "2_2") (pintype "passive"))
      (node (ref "P15") (pin "4") (pinfunction "4_4") (pintype "passive"))
      (node (ref "R25") (pin "2") (pinfunction "2_2") (pintype "passive"))
      (node (ref "R34") (pin "1") (pinfunction "1_1") (pintype "passive"))
    )
    (net (code "51") (name "/Y_LIMT") (class "Default")
      (node (ref "C30") (pin "2") (pinfunction "2_2") (pintype "passive"))
      (node (ref "P15") (pin "6") (pinfunction "6_6") (pintype "passive"))
      (node (ref "P15") (pin "8") (pinfunction "8_8") (pintype "passive"))
      (node (ref "R27") (pin "2") (pinfunction "2_2") (pintype "passive"))
      (node (ref "R35") (pin "1") (pinfunction "1_1") (pintype "passive"))
    )
    (net (code "52") (name "/Z_LIMT") (class "Default")
      (node (ref "C31") (pin "2") (pinfunction "2_2") (pintype "passive"))
      (node (ref "P15") (pin "10") (pinfunction "10_10") (pintype "passive"))
      (node (ref "P15") (pin "12") (pinfunction "12_12") (pintype "passive"))
      (node (ref "R29") (pin "2") (pinfunction "2_2") (pintype "passive"))
      (node (ref "R36") (pin "1") (pinfunction "1_1") (pintype "passive"))
    )
    (net (code "53") (name "/nRST") (class "Default")
      (node (ref "C15") (pin "2") (pinfunction "2_2") (pintype "passive"))
      (node (ref "R28") (pin "2") (pinfunction "2_2") (pintype "passive"))
      (node (ref "U4") (pin "7") (pinfunction "NRST_7") (pintype "bidirectional"))
    )
    (net (code "54") (name "3V3") (class "Default")
      (node (ref "C20") (pin "1") (pintype "passive"))
      (node (ref "C21") (pin "2") (pinfunction "2_2") (pintype "passive"))
      (node (ref "C22") (pin "2") (pinfunction "2_2") (pintype "passive"))
      (node (ref "C23") (pin "2") (pinfunction "2_2") (pintype "passive"))
      (node (ref "C3") (pin "1") (pintype "passive"))
      (node (ref "C4") (pin "2") (pinfunction "2_2") (pintype "passive"))
      (node (ref "D8") (pin "1") (pinfunction "1_1") (pintype "passive"))
      (node (ref "P5") (pin "2") (pinfunction "2_2") (pintype "passive"))
      (node (ref "R1") (pin "1") (pinfunction "1_1") (pintype "passive"))
      (node (ref "R11") (pin "2") (pinfunction "2_2") (pintype "passive"))
      (node (ref "R28") (pin "1") (pinfunction "1_1") (pintype "passive"))
      (node (ref "R34") (pin "2") (pinfunction "2_2") (pintype "passive"))
      (node (ref "R35") (pin "2") (pinfunction "2_2") (pintype "passive"))
      (node (ref "R36") (pin "2") (pinfunction "2_2") (pintype "passive"))
      (node (ref "R37") (pin "2") (pinfunction "2_2") (pintype "passive"))
      (node (ref "R38") (pin "2") (pinfunction "2_2") (pintype "passive"))
      (node (ref "R39") (pin "2") (pinfunction "2_2") (pintype "passive"))
      (node (ref "R40") (pin "2") (pinfunction "2_2") (pintype "passive"))
      (node (ref "U3") (pin "2") (pinfunction "OUT_2") (pintype "power_in"))
      (node (ref "U3") (pin "4") (pinfunction "=_4") (pintype "power_in"))
      (node (ref "U4") (pin "24") (pinfunction "VDD_1_24") (pintype "power_in"))
      (node (ref "U4") (pin "36") (pinfunction "VDD_2_36") (pintype "power_in"))
      (node (ref "U4") (pin "48") (pinfunction "VDD_3_48") (pintype "power_in"))
      (node (ref "U4") (pin "9") (pinfunction "VDDA_9") (pintype "power_in"))
    )
    (net (code "55") (name "12V") (class "Default")
      (node (ref "C10") (pin "1") (pintype "passive"))
      (node (ref "C11") (pin "2") (pinfunction "2_2") (pintype "passive"))
      (node (ref "C12") (pin "2") (pinfunction "2_2") (pintype "passive"))
      (node (ref "C24") (pin "1") (pintype "passive"))
      (node (ref "C25") (pin "2") (pinfunction "2_2") (pintype "passive"))
      (node (ref "C6") (pin "2") (pinfunction "2_2") (pintype "passive"))
      (node (ref "L1") (pin "2") (pinfunction "2_2") (pintype "passive"))
      (node (ref "P11") (pin "1") (pintype "passive"))
      (node (ref "P13") (pin "1") (pinfunction "1_1") (pintype "passive"))
      (node (ref "P7") (pin "1") (pintype "passive"))
      (node (ref "P9") (pin "2") (pintype "passive"))
      (node (ref "R3") (pin "2") (pinfunction "2_2") (pintype "passive"))
      (node (ref "U1") (pin "1") (pinfunction "VIN_1") (pintype "passive"))
    )
    (net (code "56") (name "24V") (class "Default")
      (node (ref "C1") (pin "1") (pintype "passive"))
      (node (ref "C14") (pin "2") (pinfunction "2_2") (pintype "passive"))
      (node (ref "C2") (pin "2") (pinfunction "2_2") (pintype "passive"))
      (node (ref "C5") (pin "2") (pinfunction "2_2") (pintype "passive"))
      (node (ref "C7") (pin "2") (pinfunction "2_2") (pintype "passive"))
      (node (ref "D1") (pin "2") (pinfunction "2_2") (pintype "passive"))
      (node (ref "DZ1") (pin "2") (pinfunction "2_2") (pintype "passive"))
      (node (ref "R2") (pin "1") (pinfunction "1_1") (pintype "passive"))
      (node (ref "U2") (pin "5") (pinfunction "VIN_5") (pintype "passive"))
    )
    (net (code "57") (name "48V") (class "Default")
      (node (ref "DZ3") (pin "2") (pinfunction "2_2") (pintype "passive"))
      (node (ref "P2") (pin "2") (pinfunction "2_2") (pintype "passive"))
    )
    (net (code "58") (name "GND") (class "Default")
      (node (ref "C1") (pin "2") (pintype "passive"))
      (node (ref "C10") (pin "2") (pintype "passive"))
      (node (ref "C11") (pin "1") (pinfunction "1_1") (pintype "passive"))
      (node (ref "C12") (pin "1") (pinfunction "1_1") (pintype "passive"))
      (node (ref "C14") (pin "1") (pinfunction "1_1") (pintype "passive"))
      (node (ref "C15") (pin "1") (pinfunction "1_1") (pintype "passive"))
      (node (ref "C16") (pin "2") (pinfunction "2_2") (pintype "passive"))
      (node (ref "C17") (pin "1") (pinfunction "1_1") (pintype "passive"))
      (node (ref "C18") (pin "1") (pinfunction "1_1") (pintype "passive"))
      (node (ref "C19") (pin "2") (pinfunction "2_2") (pintype "passive"))
      (node (ref "C20") (pin "2") (pintype "passive"))
      (node (ref "C21") (pin "1") (pinfunction "1_1") (pintype "passive"))
      (node (ref "C22") (pin "1") (pinfunction "1_1") (pintype "passive"))
      (node (ref "C23") (pin "1") (pinfunction "1_1") (pintype "passive"))
      (node (ref "C24") (pin "2") (pintype "passive"))
      (node (ref "C25") (pin "1") (pinfunction "1_1") (pintype "passive"))
      (node (ref "C26") (pin "2") (pintype "passive"))
      (node (ref "C27") (pin "2") (pintype "passive"))
      (node (ref "C28") (pin "2") (pintype "passive"))
      (node (ref "C29") (pin "1") (pinfunction "1_1") (pintype "passive"))
      (node (ref "C3") (pin "2") (pintype "passive"))
      (node (ref "C30") (pin "1") (pinfunction "1_1") (pintype "passive"))
      (node (ref "C31") (pin "1") (pinfunction "1_1") (pintype "passive"))
      (node (ref "C32") (pin "1") (pinfunction "1_1") (pintype "passive"))
      (node (ref "C33") (pin "1") (pinfunction "1_1") (pintype "passive"))
      (node (ref "C34") (pin "1") (pinfunction "1_1") (pintype "passive"))
      (node (ref "C35") (pin "1") (pinfunction "1_1") (pintype "passive"))
      (node (ref "C4") (pin "1") (pinfunction "1_1") (pintype "passive"))
      (node (ref "C5") (pin "1") (pinfunction "1_1") (pintype "passive"))
      (node (ref "C7") (pin "1") (pinfunction "1_1") (pintype "passive"))
      (node (ref "C8") (pin "2") (pintype "passive"))
      (node (ref "C9") (pin "1") (pinfunction "1_1") (pintype "passive"))
      (node (ref "D3") (pin "2") (pinfunction "2_2") (pintype "passive"))
      (node (ref "D4") (pin "1") (pinfunction "1_1") (pintype "passive"))
      (node (ref "D5") (pin "2") (pinfunction "2_2") (pintype "passive"))
      (node (ref "DZ1") (pin "1") (pinfunction "1_1") (pintype "passive"))
      (node (ref "DZ4") (pin "1") (pinfunction "1_1") (pintype "passive"))
      (node (ref "J1") (pin "1") (pinfunction "1_1") (pintype "passive"))
      (node (ref "J1") (pin "7") (pinfunction "7_7") (pintype "passive"))
      (node (ref "J3") (pin "1") (pinfunction "1_1") (pintype "passive"))
      (node (ref "J3") (pin "7") (pinfunction "7_7") (pintype "passive"))
      (node (ref "J5") (pin "1") (pinfunction "1_1") (pintype "passive"))
      (node (ref "J5") (pin "7") (pinfunction "7_7") (pintype "passive"))
      (node (ref "K2") (pin "2") (pinfunction "NO_2") (pintype "passive"))
      (node (ref "P1") (pin "2") (pinfunction "2_2") (pintype "passive"))
      (node (ref "P1") (pin "3") (pinfunction "3_3") (pintype "passive"))
      (node (ref "P1") (pin "4") (pinfunction "4_4") (pintype "passive"))
      (node (ref "P1") (pin "5") (pinfunction "5_5") (pintype "passive"))
      (node (ref "P11") (pin "2") (pintype "passive"))
      (node (ref "P12") (pin "2") (pinfunction "2_2") (pintype "passive"))
      (node (ref "P13") (pin "2") (pinfunction "2_2") (pintype "passive"))
      (node (ref "P14") (pin "2") (pintype "passive"))
      (node (ref "P15") (pin "1") (pinfunction "1_1") (pintype "passive"))
      (node (ref "P15") (pin "11") (pinfunction "11_11") (pintype "passive"))
      (node (ref "P15") (pin "13") (pinfunction "13_13") (pintype "passive"))
      (node (ref "P15") (pin "15") (pinfunction "15_15") (pintype "passive"))
      (node (ref "P15") (pin "17") (pinfunction "17_17") (pintype "passive"))
      (node (ref "P15") (pin "19") (pinfunction "19_19") (pintype "passive"))
      (node (ref "P15") (pin "3") (pinfunction "3_3") (pintype "passive"))
      (node (ref "P15") (pin "5") (pinfunction "5_5") (pintype "passive"))
      (node (ref "P15") (pin "7") (pinfunction "7_7") (pintype "passive"))
      (node (ref "P15") (pin "9") (pinfunction "9_9") (pintype "passive"))
      (node (ref "P2") (pin "1") (pinfunction "1_1") (pintype "passive"))
      (node (ref "P4") (pin "1") (pinfunction "EP_1") (pintype "passive"))
      (node (ref "P4") (pin "2") (pinfunction "EP_2") (pintype "passive"))
      (node (ref "P4") (pin "3") (pinfunction "EP_3") (pintype "passive"))
      (node (ref "P4") (pin "4") (pinfunction "EP_4") (pintype "passive"))
      (node (ref "P4") (pin "A1") (pinfunction "GND_A1") (pintype "passive"))
      (node (ref "P4") (pin "A12") (pinfunction "GND_A12") (pintype "passive"))
      (node (ref "P4") (pin "B1") (pinfunction "GND_B1") (pintype "passive"))
      (node (ref "P4") (pin "B12") (pinfunction "GND_B12") (pintype "passive"))
      (node (ref "P5") (pin "1") (pinfunction "1_1") (pintype "passive"))
      (node (ref "P6") (pin "1") (pinfunction "1_1") (pintype "passive"))
      (node (ref "P7") (pin "2") (pintype "passive"))
      (node (ref "P8") (pin "3") (pinfunction "3_3") (pintype "passive"))
      (node (ref "P8") (pin "4") (pinfunction "4_4") (pintype "passive"))
      (node (ref "Q1") (pin "3") (pinfunction "S_3") (pintype "passive"))
      (node (ref "Q2") (pin "3") (pinfunction "S_3") (pintype "passive"))
      (node (ref "Q3") (pin "3") (pinfunction "S_3") (pintype "passive"))
      (node (ref "R19") (pin "2") (pinfunction "2_2") (pintype "passive"))
      (node (ref "R22") (pin "1") (pinfunction "1_1") (pintype "passive"))
      (node (ref "R24") (pin "1") (pinfunction "1_1") (pintype "passive"))
      (node (ref "R31") (pin "2") (pinfunction "2_2") (pintype "passive"))
      (node (ref "R4") (pin "1") (pinfunction "1_1") (pintype "passive"))
      (node (ref "R41") (pin "2") (pinfunction "2_2") (pintype "passive"))
      (node (ref "R42") (pin "2") (pinfunction "2_2") (pintype "passive"))
      (node (ref "R43") (pin "2") (pinfunction "2_2") (pintype "passive"))
      (node (ref "R44") (pin "2") (pinfunction "2_2") (pintype "passive"))
      (node (ref "R45") (pin "2") (pinfunction "2_2") (pintype "passive"))
      (node (ref "R46") (pin "2") (pinfunction "2_2") (pintype "passive"))
      (node (ref "R47") (pin "2") (pinfunction "2_2") (pintype "passive"))
      (node (ref "R48") (pin "2") (pinfunction "2_2") (pintype "passive"))
      (node (ref "R49") (pin "2") (pinfunction "2_2") (pintype "passive"))
      (node (ref "R59") (pin "2") (pinfunction "2_2") (pintype "passive"))
      (node (ref "R80") (pin "1") (pinfunction "1_1") (pintype "passive"))
      (node (ref "U1") (pin "2") (pinfunction "GND_2") (pintype "passive"))
      (node (ref "U2") (pin "1") (pinfunction "GND_1") (pintype "passive"))
      (node (ref "U3") (pin "1") (pinfunction "GND_1") (pintype "power_in"))
      (node (ref "U4") (pin "23") (pinfunction "VSS_1_23") (pintype "power_in"))
      (node (ref "U4") (pin "35") (pinfunction "VSS_2_35") (pintype "power_in"))
      (node (ref "U4") (pin "47") (pinfunction "VSS_3_47") (pintype "power_in"))
      (node (ref "U4") (pin "8") (pinfunction "VSSA_8") (pintype "power_in"))
      (node (ref "U5") (pin "3") (pinfunction "GND_3") (pintype "passive"))
    )
    (net (code "59") (name "Net-(D1-Pad1)") (class "Default")
      (node (ref "D1") (pin "1") (pinfunction "1_1") (pintype "passive"))
      (node (ref "D2") (pin "1") (pinfunction "1_1") (pintype "passive"))
      (node (ref "K1") (pin "1") (pinfunction "1_1") (pintype "passive"))
    )
    (net (code "60") (name "Net-(D3-Pad1)") (class "Default")
      (node (ref "D3") (pin "1") (pinfunction "1_1") (pintype "passive"))
      (node (ref "R1") (pin "2") (pinfunction "2_2") (pintype "passive"))
    )
    (net (code "61") (name "Net-(D5-Pad1)") (class "Default")
      (node (ref "D5") (pin "1") (pinfunction "1_1") (pintype "passive"))
      (node (ref "R2") (pin "2") (pinfunction "2_2") (pintype "passive"))
    )
    (net (code "62") (name "Net-(D6-Pad1)") (class "Default")
      (node (ref "D6") (pin "1") (pinfunction "1_1") (pintype "passive"))
      (node (ref "R7") (pin "2") (pinfunction "2_2") (pintype "passive"))
    )
    (net (code "63") (name "Net-(D8-Pad2)") (class "Default")
      (node (ref "D8") (pin "2") (pinfunction "2_2") (pintype "passive"))
      (node (ref "R30") (pin "2") (pinfunction "2_2") (pintype "passive"))
    )
    (net (code "64") (name "Net-(D20-Pad2)") (class "Default")
      (node (ref "D20") (pin "2") (pinfunction "2_2") (pintype "passive"))
      (node (ref "R80") (pin "2") (pinfunction "2_2") (pintype "passive"))
    )
    (net (code "65") (name "Net-(J2-Pad3)") (class "Default")
      (node (ref "J2") (pin "3") (pinfunction "3_3") (pintype "passive"))
      (node (ref "J2") (pin "4") (pinfunction "4_4") (pintype "passive"))
    )
    (net (code "66") (name "Net-(J4-Pad3)") (class "Default")
      (node (ref "J4") (pin "3") (pinfunction "3_3") (pintype "passive"))
      (node (ref "J4") (pin "4") (pinfunction "4_4") (pintype "passive"))
    )
    (net (code "67") (name "Net-(J6-Pad3)") (class "Default")
      (node (ref "J6") (pin "3") (pinfunction "3_3") (pintype "passive"))
      (node (ref "J6") (pin "4") (pinfunction "4_4") (pintype "passive"))
    )
    (net (code "68") (name "Net-(K1-Pad2)") (class "Default")
      (node (ref "K1") (pin "2") (pinfunction "2_2") (pintype "passive"))
      (node (ref "P1") (pin "1") (pinfunction "1_1") (pintype "passive"))
    )
    (net (code "69") (name "Net-(Q1-D)") (class "Default")
      (node (ref "D6") (pin "2") (pinfunction "2_2") (pintype "passive"))
      (node (ref "DZ2") (pin "1") (pinfunction "1_1") (pintype "passive"))
      (node (ref "P3") (pin "2") (pintype "passive"))
      (node (ref "Q1") (pin "2") (pinfunction "D_2") (pintype "passive"))
    )
    (net (code "70") (name "Net-(Q1-G)") (class "Default")
      (node (ref "DZ4") (pin "2") (pinfunction "2_2") (pintype "passive"))
      (node (ref "Q1") (pin "1") (pinfunction "G_1") (pintype "passive"))
      (node (ref "Q2") (pin "1") (pinfunction "G_1") (pintype "passive"))
      (node (ref "R26") (pin "2") (pinfunction "2_2") (pintype "passive"))
      (node (ref "R31") (pin "1") (pinfunction "1_1") (pintype "passive"))
    )
    (net (code "71") (name "Net-(Q3-D)") (class "Default")
      (node (ref "P10") (pin "1") (pintype "passive"))
      (node (ref "P9") (pin "1") (pintype "passive"))
      (node (ref "Q3") (pin "2") (pinfunction "D_2") (pintype "passive"))
    )
    (net (code "72") (name "Net-(Q3-G)") (class "Default")
      (node (ref "Q3") (pin "1") (pinfunction "G_1") (pintype "passive"))
      (node (ref "R33") (pin "2") (pinfunction "2_2") (pintype "passive"))
    )
    (net (code "73") (name "Net-(U2-EN)") (class "Default")
      (node (ref "C2") (pin "1") (pinfunction "1_1") (pintype "passive"))
      (node (ref "U2") (pin "4") (pinfunction "EN_4") (pintype "passive"))
    )
    (net (code "74") (name "Net-(U2-FB)") (class "Default")
      (node (ref "C6") (pin "1") (pinfunction "1_1") (pintype "passive"))
      (node (ref "R3") (pin "1") (pinfunction "1_1") (pintype "passive"))
      (node (ref "R4") (pin "2") (pinfunction "2_2") (pintype "passive"))
      (node (ref "U2") (pin "2") (pinfunction "FB_2") (pintype "passive"))
    )
    (net (code "75") (name "Net-(U2-SW)") (class "Default")
      (node (ref "D4") (pin "2") (pinfunction "2_2") (pintype "passive"))
      (node (ref "L1") (pin "1") (pinfunction "1_1") (pintype "passive"))
      (node (ref "U2") (pin "3") (pinfunction "SW_3") (pintype "passive"))
    )
    (net (code "76") (name "Net-(U4-PA2)") (class "Default")
      (node (ref "R6") (pin "2") (pinfunction "2_2") (pintype "passive"))
      (node (ref "U4") (pin "12") (pinfunction "PA2_12") (pintype "bidirectional"))
    )
    (net (code "77") (name "Net-(U4-PA3)") (class "Default")
      (node (ref "R9") (pin "2") (pinfunction "2_2") (pintype "passive"))
      (node (ref "U4") (pin "13") (pinfunction "PA3_13") (pintype "bidirectional"))
    )
    (net (code "78") (name "Net-(U4-PA4)") (class "Default")
      (node (ref "R12") (pin "2") (pinfunction "2_2") (pintype "passive"))
      (node (ref "U4") (pin "14") (pinfunction "PA4_14") (pintype "bidirectional"))
    )
    (net (code "79") (name "Net-(U4-PA5)") (class "Default")
      (node (ref "R14") (pin "2") (pinfunction "2_2") (pintype "passive"))
      (node (ref "U4") (pin "15") (pinfunction "PA5_15") (pintype "bidirectional"))
    )
    (net (code "80") (name "Net-(U4-PA6)") (class "Default")
      (node (ref "R16") (pin "2") (pinfunction "2_2") (pintype "passive"))
      (node (ref "U4") (pin "16") (pinfunction "PA6_16") (pintype "bidirectional"))
    )
    (net (code "81") (name "Net-(U4-PA7)") (class "Default")
      (node (ref "R18") (pin "2") (pinfunction "2_2") (pintype "passive"))
      (node (ref "U4") (pin "17") (pinfunction "PA7_17") (pintype "bidirectional"))
    )
    (net (code "82") (name "Net-(U4-PA8)") (class "Default")
      (node (ref "R20") (pin "2") (pinfunction "2_2") (pintype "passive"))
      (node (ref "U4") (pin "29") (pinfunction "PA8_29") (pintype "bidirectional"))
    )
    (net (code "83") (name "Net-(U4-PA9)") (class "Default")
      (node (ref "R21") (pin "2") (pinfunction "2_2") (pintype "passive"))
      (node (ref "U4") (pin "30") (pinfunction "PA9_30") (pintype "bidirectional"))
    )
    (net (code "84") (name "Net-(U4-PA10)") (class "Default")
      (node (ref "R23") (pin "2") (pinfunction "2_2") (pintype "passive"))
      (node (ref "U4") (pin "31") (pinfunction "PA10_31") (pintype "bidirectional"))
    )
    (net (code "85") (name "Net-(U4-PA15{slash}JTDI)") (class "Default")
      (node (ref "R30") (pin "1") (pinfunction "1_1") (pintype "passive"))
      (node (ref "U4") (pin "38") (pinfunction "PA15/JTDI_38") (pintype "bidirectional"))
    )
    (net (code "86") (name "Net-(U4-PB0)") (class "Default")
      (node (ref "R5") (pin "1") (pinfunction "1_1") (pintype "passive"))
      (node (ref "U4") (pin "18") (pinfunction "PB0_18") (pintype "bidirectional"))
    )
    (net (code "87") (name "Net-(U4-PB3{slash}JTDO)") (class "Default")
      (node (ref "R10") (pin "1") (pinfunction "1_1") (pintype "passive"))
      (node (ref "U4") (pin "39") (pinfunction "PB3/JTDO_39") (pintype "bidirectional"))
    )
    (net (code "88") (name "Net-(U4-PB4{slash}JNTRST)") (class "Default")
      (node (ref "R13") (pin "1") (pinfunction "1_1") (pintype "passive"))
      (node (ref "U4") (pin "40") (pinfunction "PB4/JNTRST_40") (pintype "bidirectional"))
    )
    (net (code "89") (name "Net-(U4-PB5)") (class "Default")
      (node (ref "R15") (pin "1") (pinfunction "1_1") (pintype "passive"))
      (node (ref "U4") (pin "41") (pinfunction "PB5_41") (pintype "bidirectional"))
    )
    (net (code "90") (name "Net-(U4-PB6)") (class "Default")
      (node (ref "R17") (pin "1") (pinfunction "1_1") (pintype "passive"))
      (node (ref "U4") (pin "42") (pinfunction "PB6_42") (pintype "bidirectional"))
    )
    (net (code "91") (name "Net-(U4-PB12)") (class "Default")
      (node (ref "R25") (pin "1") (pinfunction "1_1") (pintype "passive"))
      (node (ref "U4") (pin "25") (pinfunction "PB12_25") (pintype "bidirectional"))
    )
    (net (code "92") (name "Net-(U4-PB13)") (class "Default")
      (node (ref "R27") (pin "1") (pinfunction "1_1") (pintype "passive"))
      (node (ref "U4") (pin "26") (pinfunction "PB13_26") (pintype "bidirectional"))
    )
    (net (code "93") (name "Net-(U4-PB14)") (class "Default")
      (node (ref "R29") (pin "1") (pinfunction "1_1") (pintype "passive"))
      (node (ref "U4") (pin "27") (pinfunction "PB14_27") (pintype "bidirectional"))
    )
    (net (code "94") (name "Net-(U5-Y)") (class "Default")
      (node (ref "R26") (pin "1") (pinfunction "1_1") (pintype "passive"))
      (node (ref "U5") (pin "4") (pinfunction "Y_4") (pintype "passive"))
    )
    (net (code "95") (name "USB-CHK") (class "Default")
      (node (ref "R50") (pin "2") (pinfunction "2_2") (pintype "passive"))
      (node (ref "R59") (pin "1") (pinfunction "1_1") (pintype "passive"))
      (node (ref "U4") (pin "19") (pinfunction "PB1_19") (pintype "bidirectional"))
    )
    (net (code "96") (name "VCC") (class "Default")
      (node (ref "C18") (pin "2") (pinfunction "2_2") (pintype "passive"))
      (node (ref "C8") (pin "1") (pintype "passive"))
      (node (ref "C9") (pin "2") (pinfunction "2_2") (pintype "passive"))
      (node (ref "D9") (pin "2") (pinfunction "2_2") (pintype "passive"))
      (node (ref "J1") (pin "2") (pinfunction "2_2") (pintype "passive"))
      (node (ref "J3") (pin "2") (pinfunction "2_2") (pintype "passive"))
      (node (ref "J5") (pin "2") (pinfunction "2_2") (pintype "passive"))
      (node (ref "J7") (pin "4") (pinfunction "4_4") (pintype "passive"))
      (node (ref "J7") (pin "5") (pinfunction "5_5") (pintype "passive"))
      (node (ref "J7") (pin "6") (pinfunction "6_6") (pintype "passive"))
      (node (ref "J8") (pin "4") (pinfunction "4_4") (pintype "passive"))
      (node (ref "J8") (pin "5") (pinfunction "5_5") (pintype "passive"))
      (node (ref "J8") (pin "6") (pinfunction "6_6") (pintype "passive"))
      (node (ref "J9") (pin "4") (pinfunction "4_4") (pintype "passive"))
      (node (ref "J9") (pin "5") (pinfunction "5_5") (pintype "passive"))
      (node (ref "J9") (pin "6") (pinfunction "6_6") (pintype "passive"))
      (node (ref "P10") (pin "2") (pintype "passive"))
      (node (ref "P12") (pin "1") (pinfunction "1_1") (pintype "passive"))
      (node (ref "P17") (pin "2") (pinfunction "2_2") (pintype "passive"))
      (node (ref "P17") (pin "4") (pinfunction "4_4") (pintype "passive"))
      (node (ref "P20") (pin "2") (pinfunction "2_2") (pintype "passive"))
      (node (ref "P20") (pin "4") (pinfunction "4_4") (pintype "passive"))
      (node (ref "P22") (pin "2") (pinfunction "2_2") (pintype "passive"))
      (node (ref "P22") (pin "4") (pinfunction "4_4") (pintype "passive"))
      (node (ref "P6") (pin "2") (pinfunction "2_2") (pintype "passive"))
      (node (ref "P8") (pin "1") (pinfunction "1_1") (pintype "passive"))
      (node (ref "P8") (pin "2") (pinfunction "2_2") (pintype "passive"))
      (node (ref "U1") (pin "3") (pinfunction "VOUT_3") (pintype "passive"))
      (node (ref "U3") (pin "3") (pinfunction "IN_3") (pintype "power_in"))
      (node (ref "U5") (pin "5") (pinfunction "VCC_5") (pintype "passive"))
    )
    (net (code "97") (name "VSPN") (class "Default")
      (node (ref "C26") (pin "1") (pintype "passive"))
      (node (ref "C27") (pin "1") (pintype "passive"))
      (node (ref "C28") (pin "1") (pintype "passive"))
      (node (ref "D2") (pin "2") (pinfunction "2_2") (pintype "passive"))
      (node (ref "DZ2") (pin "2") (pinfunction "2_2") (pintype "passive"))
      (node (ref "J1") (pin "8") (pinfunction "8_8") (pintype "passive"))
      (node (ref "J3") (pin "8") (pinfunction "8_8") (pintype "passive"))
      (node (ref "J5") (pin "8") (pinfunction "8_8") (pintype "passive"))
      (node (ref "P3") (pin "1") (pintype "passive"))
      (node (ref "R7") (pin "1") (pinfunction "1_1") (pintype "passive"))
    )
    (net (code "98") (name "VUSB") (class "Default")
      (node (ref "C17") (pin "2") (pinfunction "2_2") (pintype "passive"))
      (node (ref "D20") (pin "1") (pinfunction "1_1") (pintype "passive"))
      (node (ref "D9") (pin "1") (pinfunction "1_1") (pintype "passive"))
      (node (ref "P4") (pin "A4") (pinfunction "VBUS_A4") (pintype "passive"))
      (node (ref "P4") (pin "A9") (pinfunction "VBUS_A9") (pintype "passive"))
      (node (ref "P4") (pin "B4") (pinfunction "VBUS_B4") (pintype "passive"))
      (node (ref "P4") (pin "B9") (pinfunction "VBUS_B9") (pintype "passive"))
      (node (ref "R32") (pin "1") (pinfunction "1_1") (pintype "passive"))
      (node (ref "R50") (pin "1") (pinfunction "1_1") (pintype "passive"))
    )
    (net (code "99") (name "unconnected-(K1-Pad3)") (class "Default")
      (node (ref "K1") (pin "3") (pinfunction "3_3") (pintype "passive"))
    )
    (net (code "100") (name "unconnected-(K1-Pad4)") (class "Default")
      (node (ref "K1") (pin "4") (pinfunction "4_4") (pintype "passive"))
    )
    (net (code "101") (name "unconnected-(K1-Pad5)") (class "Default")
      (node (ref "K1") (pin "5") (pinfunction "5_5") (pintype "passive"))
    )
    (net (code "102") (name "unconnected-(P4-CC1-PadA5)") (class "Default")
      (node (ref "P4") (pin "A5") (pinfunction "CC1_A5") (pintype "passive"))
    )
    (net (code "103") (name "unconnected-(P4-CC2-PadB5)") (class "Default")
      (node (ref "P4") (pin "B5") (pinfunction "CC2_B5") (pintype "passive"))
    )
    (net (code "104") (name "unconnected-(P4-SUB1-PadA8)") (class "Default")
      (node (ref "P4") (pin "A8") (pinfunction "SUB1_A8") (pintype "passive"))
    )
    (net (code "105") (name "unconnected-(P4-SUB2-PadB8)") (class "Default")
      (node (ref "P4") (pin "B8") (pinfunction "SUB2_B8") (pintype "passive"))
    )
    (net (code "106") (name "unconnected-(P8-Pad7)") (class "Default")
      (node (ref "P8") (pin "7") (pinfunction "7_7") (pintype "passive"))
    )
    (net (code "107") (name "unconnected-(U4-PB7-Pad43)") (class "Default")
      (node (ref "U4") (pin "43") (pinfunction "PB7_43") (pintype "bidirectional"))
    )
    (net (code "108") (name "unconnected-(U4-PB8-Pad45)") (class "Default")
      (node (ref "U4") (pin "45") (pinfunction "PB8_45") (pintype "bidirectional"))
    )
    (net (code "109") (name "unconnected-(U4-PB9-Pad46)") (class "Default")
      (node (ref "U4") (pin "46") (pinfunction "PB9_46") (pintype "bidirectional"))
    )
    (net (code "110") (name "unconnected-(U4-PB10-Pad21)") (class "Default")
      (node (ref "U4") (pin "21") (pinfunction "PB10_21") (pintype "bidirectional"))
    )
    (net (code "111") (name "unconnected-(U4-PB11-Pad22)") (class "Default")
      (node (ref "U4") (pin "22") (pinfunction "PB11_22") (pintype "bidirectional"))
    )
    (net (code "112") (name "unconnected-(U4-PC13-TAMPER-RTC-Pad2)") (class "Default")
      (node (ref "U4") (pin "2") (pinfunction "PC13-TAMPER-RTC_2") (pintype "bidirectional"))
    )
    (net (code "113") (name "unconnected-(U4-PC14-OSC32_IN-Pad3)") (class "Default")
      (node (ref "U4") (pin "3") (pinfunction "PC14-OSC32_IN_3") (pintype "bidirectional"))
    )
    (net (code "114") (name "unconnected-(U4-PC15-OSC32_OUT-Pad4)") (class "Default")
      (node (ref "U4") (pin "4") (pinfunction "PC15-OSC32_OUT_4") (pintype "bidirectional"))
    )
    (net (code "115") (name "unconnected-(U4-VBAT-Pad1)") (class "Default")
      (node (ref "U4") (pin "1") (pinfunction "VBAT_1") (pintype "power_in"))
    )
    (net (code "116") (name "unconnected-(U5-NC-Pad1)") (class "Default")
      (node (ref "U5") (pin "1") (pinfunction "NC_1") (pintype "passive"))
    )
  )
)
